# IOP_1_1.net
KiCad netlist of a schematic drawn in EAGLE
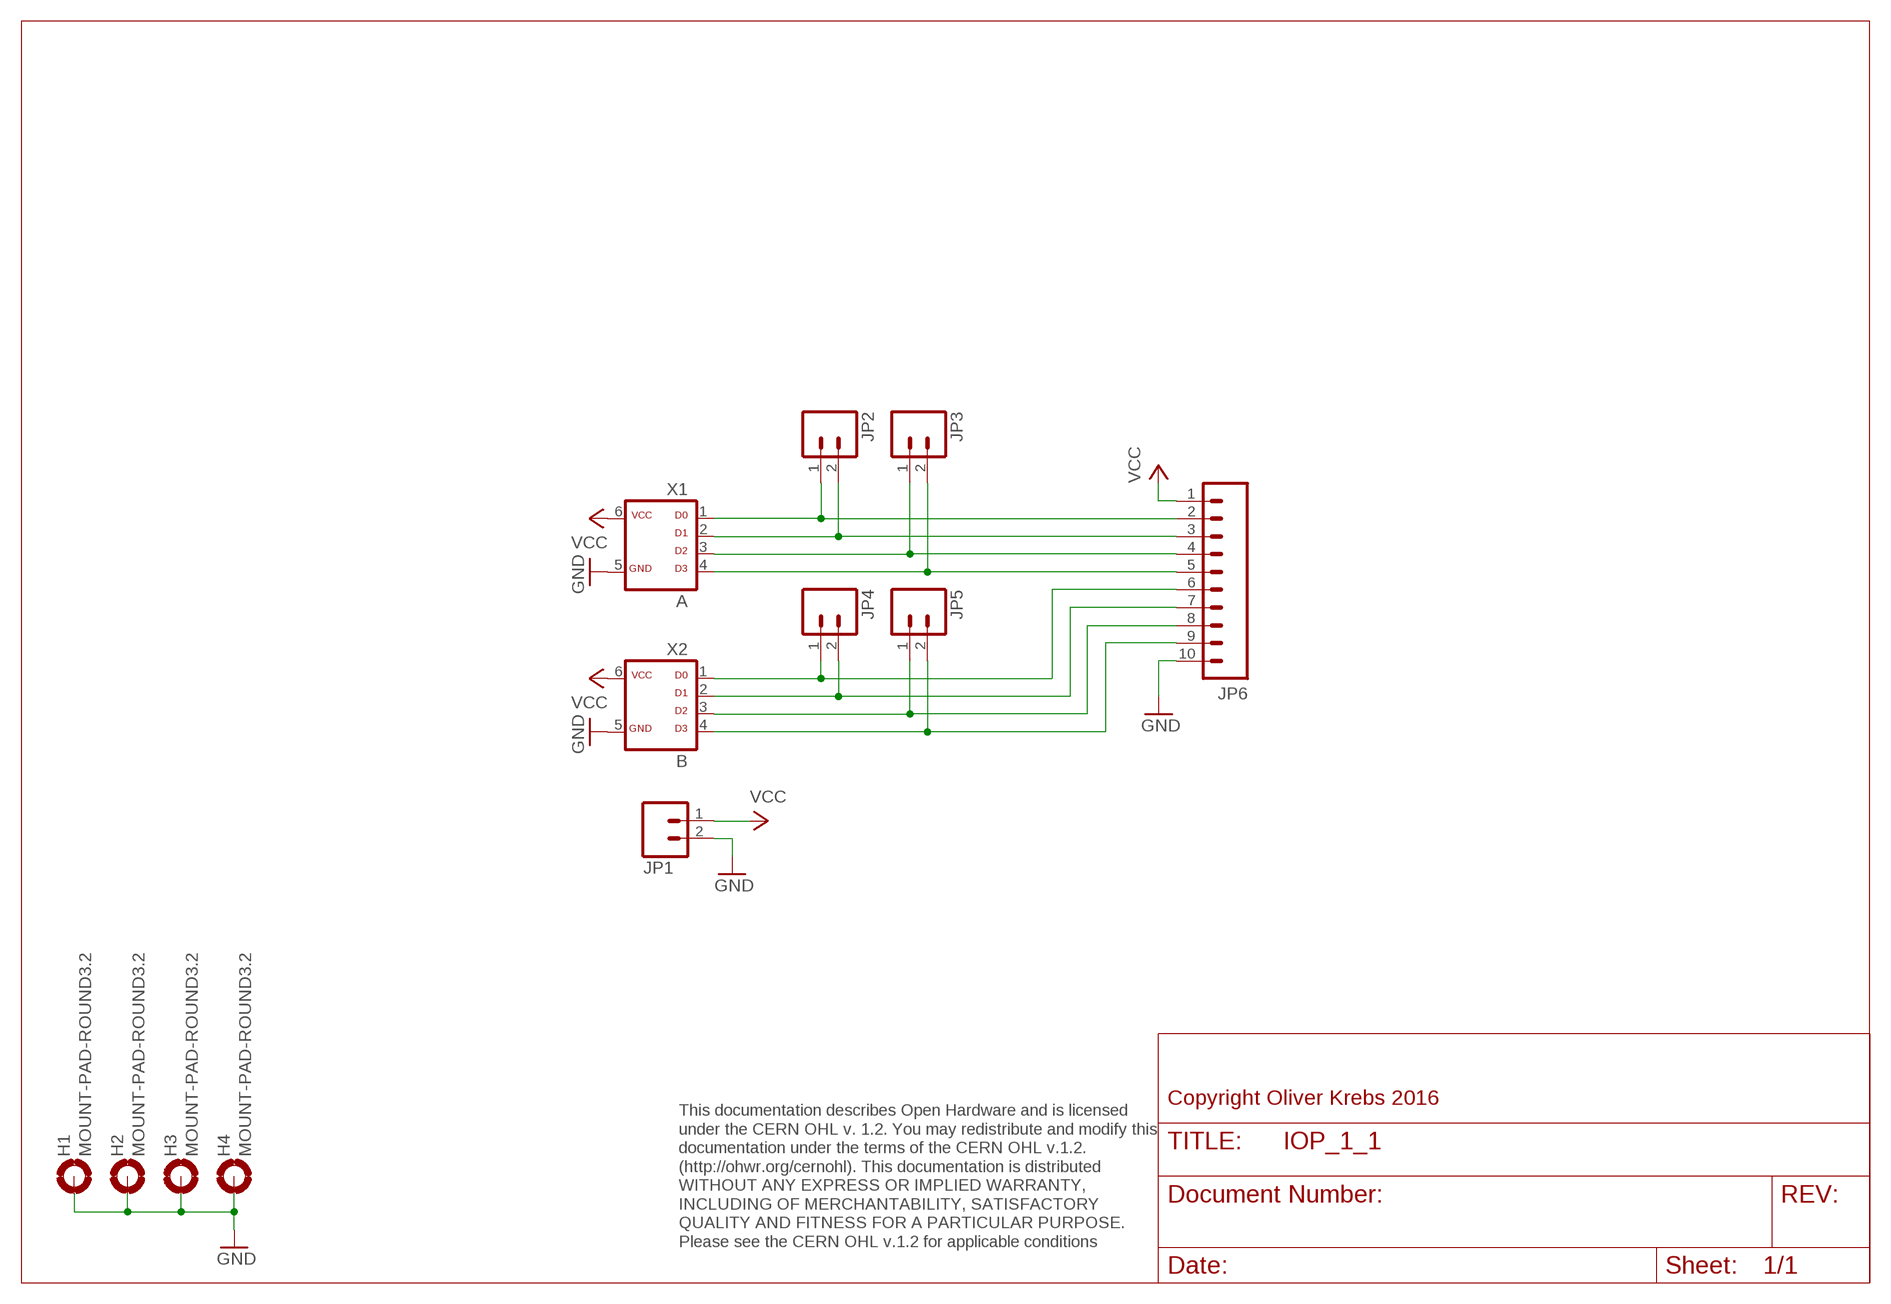
[diagram p0: schematic, sheet 1]

(export (version "E")
  (design (tool "Eeschema 10.0.6"))
  (components
    (comp (ref "H1")
      (value "MOUNT-PAD-ROUND3.2")
      (footprint "eagle-import:3,2-PAD")
      (libsource (lib "eagle-import") (part "MOUNT-PAD-ROUND3.2"))
    )
    (comp (ref "H2")
      (value "MOUNT-PAD-ROUND3.2")
      (footprint "eagle-import:3,2-PAD")
      (libsource (lib "eagle-import") (part "MOUNT-PAD-ROUND3.2"))
    )
    (comp (ref "H3")
      (value "MOUNT-PAD-ROUND3.2")
      (footprint "eagle-import:3,2-PAD")
      (libsource (lib "eagle-import") (part "MOUNT-PAD-ROUND3.2"))
    )
    (comp (ref "H4")
      (value "MOUNT-PAD-ROUND3.2")
      (footprint "eagle-import:3,2-PAD")
      (libsource (lib "eagle-import") (part "MOUNT-PAD-ROUND3.2"))
    )
    (comp (ref "JP1")
      (value "M021.3MM-5.08")
      (footprint "eagle-import:1X02_BIG_5.08")
      (libsource (lib "eagle-import") (part "M021.3MM-5.08"))
    )
    (comp (ref "JP2")
      (value "M021.3MM-5.08")
      (footprint "eagle-import:1X02_BIG_5.08")
      (libsource (lib "eagle-import") (part "M021.3MM-5.08"))
    )
    (comp (ref "JP3")
      (value "M021.3MM-5.08")
      (footprint "eagle-import:1X02_BIG_5.08")
      (libsource (lib "eagle-import") (part "M021.3MM-5.08"))
    )
    (comp (ref "JP4")
      (value "M021.3MM-5.08")
      (footprint "eagle-import:1X02_BIG_5.08")
      (libsource (lib "eagle-import") (part "M021.3MM-5.08"))
    )
    (comp (ref "JP5")
      (value "M021.3MM-5.08")
      (footprint "eagle-import:1X02_BIG_5.08")
      (libsource (lib "eagle-import") (part "M021.3MM-5.08"))
    )
    (comp (ref "JP6")
      (value "M10SILK_FEMALE_PTH")
      (footprint "eagle-import:1X10")
      (libsource (lib "eagle-import") (part "M10SILK_FEMALE_PTH"))
    )
    (comp (ref "X1")
      (value "A")
      (footprint "eagle-import:ML-6")
      (libsource (lib "eagle-import") (part "ML6D"))
    )
    (comp (ref "X2")
      (value "B")
      (footprint "eagle-import:ML-6")
      (libsource (lib "eagle-import") (part "ML6D"))
    )
  )
  (nets
    (net (code "1") (name "GND") (class "Default")
      (node (ref "H1") (pin "B3,2") (pinfunction "MOUNT_B3,2") (pintype "passive"))
      (node (ref "H2") (pin "B3,2") (pinfunction "MOUNT_B3,2") (pintype "passive"))
      (node (ref "H3") (pin "B3,2") (pinfunction "MOUNT_B3,2") (pintype "passive"))
      (node (ref "H4") (pin "B3,2") (pinfunction "MOUNT_B3,2") (pintype "passive"))
      (node (ref "JP1") (pin "2") (pinfunction "2_2") (pintype "passive"))
      (node (ref "JP6") (pin "10") (pinfunction "10_10") (pintype "passive"))
      (node (ref "X1") (pin "5") (pinfunction "5_5") (pintype "passive"))
      (node (ref "X2") (pin "5") (pinfunction "5_5") (pintype "passive"))
    )
    (net (code "2") (name "Net-(JP2-Pad1)") (class "Default")
      (node (ref "JP2") (pin "1") (pinfunction "1_1") (pintype "passive"))
      (node (ref "JP6") (pin "2") (pinfunction "2_2") (pintype "passive"))
      (node (ref "X1") (pin "1") (pinfunction "1_1") (pintype "passive"))
    )
    (net (code "3") (name "Net-(JP2-Pad2)") (class "Default")
      (node (ref "JP2") (pin "2") (pinfunction "2_2") (pintype "passive"))
      (node (ref "JP6") (pin "3") (pinfunction "3_3") (pintype "passive"))
      (node (ref "X1") (pin "2") (pinfunction "2_2") (pintype "passive"))
    )
    (net (code "4") (name "Net-(JP3-Pad1)") (class "Default")
      (node (ref "JP3") (pin "1") (pinfunction "1_1") (pintype "passive"))
      (node (ref "JP6") (pin "4") (pinfunction "4_4") (pintype "passive"))
      (node (ref "X1") (pin "3") (pinfunction "3_3") (pintype "passive"))
    )
    (net (code "5") (name "Net-(JP3-Pad2)") (class "Default")
      (node (ref "JP3") (pin "2") (pinfunction "2_2") (pintype "passive"))
      (node (ref "JP6") (pin "5") (pinfunction "5_5") (pintype "passive"))
      (node (ref "X1") (pin "4") (pinfunction "4_4") (pintype "passive"))
    )
    (net (code "6") (name "Net-(JP4-Pad1)") (class "Default")
      (node (ref "JP4") (pin "1") (pinfunction "1_1") (pintype "passive"))
      (node (ref "JP6") (pin "6") (pinfunction "6_6") (pintype "passive"))
      (node (ref "X2") (pin "1") (pinfunction "1_1") (pintype "passive"))
    )
    (net (code "7") (name "Net-(JP4-Pad2)") (class "Default")
      (node (ref "JP4") (pin "2") (pinfunction "2_2") (pintype "passive"))
      (node (ref "JP6") (pin "7") (pinfunction "7_7") (pintype "passive"))
      (node (ref "X2") (pin "2") (pinfunction "2_2") (pintype "passive"))
    )
    (net (code "8") (name "Net-(JP5-Pad1)") (class "Default")
      (node (ref "JP5") (pin "1") (pinfunction "1_1") (pintype "passive"))
      (node (ref "JP6") (pin "8") (pinfunction "8_8") (pintype "passive"))
      (node (ref "X2") (pin "3") (pinfunction "3_3") (pintype "passive"))
    )
    (net (code "9") (name "Net-(JP5-Pad2)") (class "Default")
      (node (ref "JP5") (pin "2") (pinfunction "2_2") (pintype "passive"))
      (node (ref "JP6") (pin "9") (pinfunction "9_9") (pintype "passive"))
      (node (ref "X2") (pin "4") (pinfunction "4_4") (pintype "passive"))
    )
    (net (code "10") (name "VCC") (class "Default")
      (node (ref "JP1") (pin "1") (pinfunction "1_1") (pintype "passive"))
      (node (ref "JP6") (pin "1") (pinfunction "1_1") (pintype "passive"))
      (node (ref "X1") (pin "6") (pinfunction "6_6") (pintype "passive"))
      (node (ref "X2") (pin "6") (pinfunction "6_6") (pintype "passive"))
    )
  )
)
